# stm32f4-discovery-breakout-v1.net
KiCad netlist of a schematic drawn in EAGLE
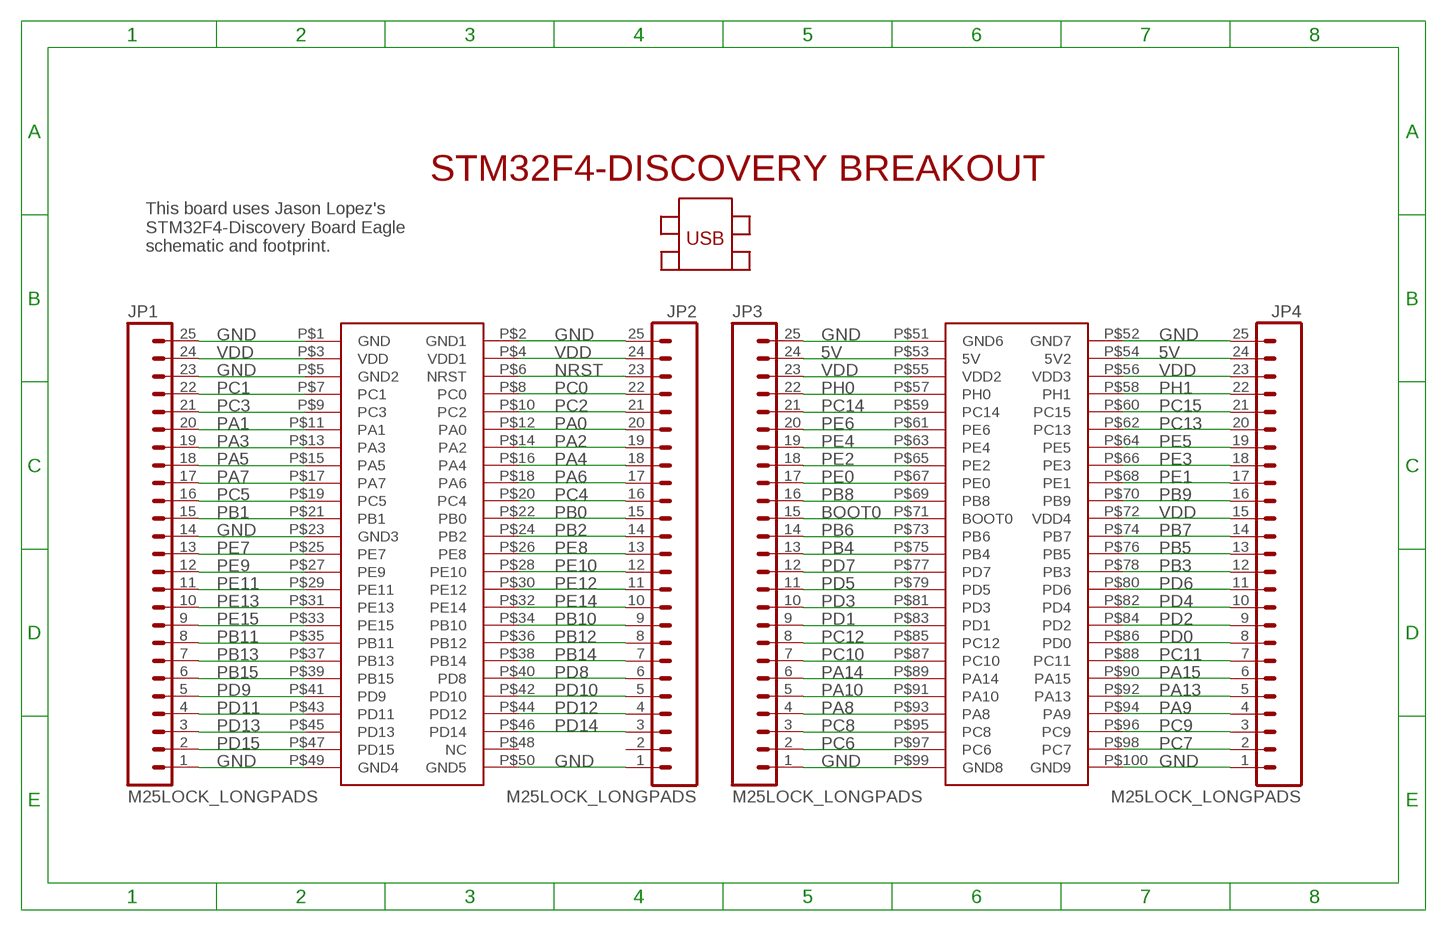
[diagram p0: schematic, sheet 1]

(export (version "E")
  (design (tool "Eeschema 10.0.6"))
  (components
    (comp (ref "JP1")
      (value "M25LOCK_LONGPADS")
      (footprint "eagle-import:1X25_LOCK_LONGPADS")
      (libsource (lib "eagle-import") (part "M25LOCK_LONGPADS"))
    )
    (comp (ref "JP2")
      (value "M25LOCK_LONGPADS")
      (footprint "eagle-import:1X25_LOCK_LONGPADS")
      (libsource (lib "eagle-import") (part "M25LOCK_LONGPADS"))
    )
    (comp (ref "JP3")
      (value "M25LOCK_LONGPADS")
      (footprint "eagle-import:1X25_LOCK_LONGPADS")
      (libsource (lib "eagle-import") (part "M25LOCK_LONGPADS"))
    )
    (comp (ref "JP4")
      (value "M25LOCK_LONGPADS")
      (footprint "eagle-import:1X25_LOCK_LONGPADS")
      (libsource (lib "eagle-import") (part "M25LOCK_LONGPADS"))
    )
    (comp (ref "U$1")
      (value "STM32F4-DISCOVERY")
      (footprint "eagle-import:STM32F4-DISCOVERY")
      (libsource (lib "eagle-import") (part "STM32F4-DISCOVERY"))
    )
  )
  (nets
    (net (code "1") (name "/5V") (class "Default")
      (node (ref "JP3") (pin "24") (pinfunction "24_24") (pintype "passive"))
      (node (ref "JP4") (pin "24") (pinfunction "24_24") (pintype "passive"))
      (node (ref "U$1") (pin "P$53") (pinfunction "5V_P$53") (pintype "bidirectional"))
      (node (ref "U$1") (pin "P$54") (pinfunction "5V2_P$54") (pintype "bidirectional"))
    )
    (net (code "2") (name "/BOOT0") (class "Default")
      (node (ref "JP3") (pin "15") (pinfunction "15_15") (pintype "passive"))
      (node (ref "U$1") (pin "P$71") (pinfunction "BOOT0_P$71") (pintype "bidirectional"))
    )
    (net (code "3") (name "/GND") (class "Default")
      (node (ref "JP1") (pin "1") (pinfunction "1_1") (pintype "passive"))
      (node (ref "JP1") (pin "14") (pinfunction "14_14") (pintype "passive"))
      (node (ref "JP1") (pin "23") (pinfunction "23_23") (pintype "passive"))
      (node (ref "JP1") (pin "25") (pinfunction "25_25") (pintype "passive"))
      (node (ref "JP2") (pin "1") (pinfunction "1_1") (pintype "passive"))
      (node (ref "JP2") (pin "25") (pinfunction "25_25") (pintype "passive"))
      (node (ref "JP3") (pin "1") (pinfunction "1_1") (pintype "passive"))
      (node (ref "JP3") (pin "25") (pinfunction "25_25") (pintype "passive"))
      (node (ref "JP4") (pin "1") (pinfunction "1_1") (pintype "passive"))
      (node (ref "JP4") (pin "25") (pinfunction "25_25") (pintype "passive"))
      (node (ref "U$1") (pin "P$1") (pinfunction "GND_P$1") (pintype "bidirectional"))
      (node (ref "U$1") (pin "P$100") (pinfunction "GND9_P$100") (pintype "bidirectional"))
      (node (ref "U$1") (pin "P$2") (pinfunction "GND1_P$2") (pintype "bidirectional"))
      (node (ref "U$1") (pin "P$23") (pinfunction "GND3_P$23") (pintype "bidirectional"))
      (node (ref "U$1") (pin "P$49") (pinfunction "GND4_P$49") (pintype "bidirectional"))
      (node (ref "U$1") (pin "P$5") (pinfunction "GND2_P$5") (pintype "bidirectional"))
      (node (ref "U$1") (pin "P$50") (pinfunction "GND5_P$50") (pintype "bidirectional"))
      (node (ref "U$1") (pin "P$51") (pinfunction "GND6_P$51") (pintype "bidirectional"))
      (node (ref "U$1") (pin "P$52") (pinfunction "GND7_P$52") (pintype "bidirectional"))
      (node (ref "U$1") (pin "P$99") (pinfunction "GND8_P$99") (pintype "bidirectional"))
    )
    (net (code "4") (name "/NRST") (class "Default")
      (node (ref "JP2") (pin "23") (pinfunction "23_23") (pintype "passive"))
      (node (ref "U$1") (pin "P$6") (pinfunction "NRST_P$6") (pintype "bidirectional"))
    )
    (net (code "5") (name "/PA0") (class "Default")
      (node (ref "JP2") (pin "20") (pinfunction "20_20") (pintype "passive"))
      (node (ref "U$1") (pin "P$12") (pinfunction "PA0_P$12") (pintype "bidirectional"))
    )
    (net (code "6") (name "/PA1") (class "Default")
      (node (ref "JP1") (pin "20") (pinfunction "20_20") (pintype "passive"))
      (node (ref "U$1") (pin "P$11") (pinfunction "PA1_P$11") (pintype "bidirectional"))
    )
    (net (code "7") (name "/PA2") (class "Default")
      (node (ref "JP2") (pin "19") (pinfunction "19_19") (pintype "passive"))
      (node (ref "U$1") (pin "P$14") (pinfunction "PA2_P$14") (pintype "bidirectional"))
    )
    (net (code "8") (name "/PA3") (class "Default")
      (node (ref "JP1") (pin "19") (pinfunction "19_19") (pintype "passive"))
      (node (ref "U$1") (pin "P$13") (pinfunction "PA3_P$13") (pintype "bidirectional"))
    )
    (net (code "9") (name "/PA4") (class "Default")
      (node (ref "JP2") (pin "18") (pinfunction "18_18") (pintype "passive"))
      (node (ref "U$1") (pin "P$16") (pinfunction "PA4_P$16") (pintype "bidirectional"))
    )
    (net (code "10") (name "/PA5") (class "Default")
      (node (ref "JP1") (pin "18") (pinfunction "18_18") (pintype "passive"))
      (node (ref "U$1") (pin "P$15") (pinfunction "PA5_P$15") (pintype "bidirectional"))
    )
    (net (code "11") (name "/PA6") (class "Default")
      (node (ref "JP2") (pin "17") (pinfunction "17_17") (pintype "passive"))
      (node (ref "U$1") (pin "P$18") (pinfunction "PA6_P$18") (pintype "bidirectional"))
    )
    (net (code "12") (name "/PA7") (class "Default")
      (node (ref "JP1") (pin "17") (pinfunction "17_17") (pintype "passive"))
      (node (ref "U$1") (pin "P$17") (pinfunction "PA7_P$17") (pintype "bidirectional"))
    )
    (net (code "13") (name "/PA8") (class "Default")
      (node (ref "JP3") (pin "4") (pinfunction "4_4") (pintype "passive"))
      (node (ref "U$1") (pin "P$93") (pinfunction "PA8_P$93") (pintype "bidirectional"))
    )
    (net (code "14") (name "/PA9") (class "Default")
      (node (ref "JP4") (pin "4") (pinfunction "4_4") (pintype "passive"))
      (node (ref "U$1") (pin "P$94") (pinfunction "PA9_P$94") (pintype "bidirectional"))
    )
    (net (code "15") (name "/PA10") (class "Default")
      (node (ref "JP3") (pin "5") (pinfunction "5_5") (pintype "passive"))
      (node (ref "U$1") (pin "P$91") (pinfunction "PA10_P$91") (pintype "bidirectional"))
    )
    (net (code "16") (name "/PA13") (class "Default")
      (node (ref "JP4") (pin "5") (pinfunction "5_5") (pintype "passive"))
      (node (ref "U$1") (pin "P$92") (pinfunction "PA13_P$92") (pintype "bidirectional"))
    )
    (net (code "17") (name "/PA14") (class "Default")
      (node (ref "JP3") (pin "6") (pinfunction "6_6") (pintype "passive"))
      (node (ref "U$1") (pin "P$89") (pinfunction "PA14_P$89") (pintype "bidirectional"))
    )
    (net (code "18") (name "/PA15") (class "Default")
      (node (ref "JP4") (pin "6") (pinfunction "6_6") (pintype "passive"))
      (node (ref "U$1") (pin "P$90") (pinfunction "PA15_P$90") (pintype "bidirectional"))
    )
    (net (code "19") (name "/PB0") (class "Default")
      (node (ref "JP2") (pin "15") (pinfunction "15_15") (pintype "passive"))
      (node (ref "U$1") (pin "P$22") (pinfunction "PB0_P$22") (pintype "bidirectional"))
    )
    (net (code "20") (name "/PB1") (class "Default")
      (node (ref "JP1") (pin "15") (pinfunction "15_15") (pintype "passive"))
      (node (ref "U$1") (pin "P$21") (pinfunction "PB1_P$21") (pintype "bidirectional"))
    )
    (net (code "21") (name "/PB2") (class "Default")
      (node (ref "JP2") (pin "14") (pinfunction "14_14") (pintype "passive"))
      (node (ref "U$1") (pin "P$24") (pinfunction "PB2_P$24") (pintype "bidirectional"))
    )
    (net (code "22") (name "/PB3") (class "Default")
      (node (ref "JP4") (pin "12") (pinfunction "12_12") (pintype "passive"))
      (node (ref "U$1") (pin "P$78") (pinfunction "PB3_P$78") (pintype "bidirectional"))
    )
    (net (code "23") (name "/PB4") (class "Default")
      (node (ref "JP3") (pin "13") (pinfunction "13_13") (pintype "passive"))
      (node (ref "U$1") (pin "P$75") (pinfunction "PB4_P$75") (pintype "bidirectional"))
    )
    (net (code "24") (name "/PB5") (class "Default")
      (node (ref "JP4") (pin "13") (pinfunction "13_13") (pintype "passive"))
      (node (ref "U$1") (pin "P$76") (pinfunction "PB5_P$76") (pintype "bidirectional"))
    )
    (net (code "25") (name "/PB6") (class "Default")
      (node (ref "JP3") (pin "14") (pinfunction "14_14") (pintype "passive"))
      (node (ref "U$1") (pin "P$73") (pinfunction "PB6_P$73") (pintype "bidirectional"))
    )
    (net (code "26") (name "/PB7") (class "Default")
      (node (ref "JP4") (pin "14") (pinfunction "14_14") (pintype "passive"))
      (node (ref "U$1") (pin "P$74") (pinfunction "PB7_P$74") (pintype "bidirectional"))
    )
    (net (code "27") (name "/PB8") (class "Default")
      (node (ref "JP3") (pin "16") (pinfunction "16_16") (pintype "passive"))
      (node (ref "U$1") (pin "P$69") (pinfunction "PB8_P$69") (pintype "bidirectional"))
    )
    (net (code "28") (name "/PB9") (class "Default")
      (node (ref "JP4") (pin "16") (pinfunction "16_16") (pintype "passive"))
      (node (ref "U$1") (pin "P$70") (pinfunction "PB9_P$70") (pintype "bidirectional"))
    )
    (net (code "29") (name "/PB10") (class "Default")
      (node (ref "JP2") (pin "9") (pinfunction "9_9") (pintype "passive"))
      (node (ref "U$1") (pin "P$34") (pinfunction "PB10_P$34") (pintype "bidirectional"))
    )
    (net (code "30") (name "/PB11") (class "Default")
      (node (ref "JP1") (pin "8") (pinfunction "8_8") (pintype "passive"))
      (node (ref "U$1") (pin "P$35") (pinfunction "PB11_P$35") (pintype "bidirectional"))
    )
    (net (code "31") (name "/PB12") (class "Default")
      (node (ref "JP2") (pin "8") (pinfunction "8_8") (pintype "passive"))
      (node (ref "U$1") (pin "P$36") (pinfunction "PB12_P$36") (pintype "bidirectional"))
    )
    (net (code "32") (name "/PB13") (class "Default")
      (node (ref "JP1") (pin "7") (pinfunction "7_7") (pintype "passive"))
      (node (ref "U$1") (pin "P$37") (pinfunction "PB13_P$37") (pintype "bidirectional"))
    )
    (net (code "33") (name "/PB14") (class "Default")
      (node (ref "JP2") (pin "7") (pinfunction "7_7") (pintype "passive"))
      (node (ref "U$1") (pin "P$38") (pinfunction "PB14_P$38") (pintype "bidirectional"))
    )
    (net (code "34") (name "/PB15") (class "Default")
      (node (ref "JP1") (pin "6") (pinfunction "6_6") (pintype "passive"))
      (node (ref "U$1") (pin "P$39") (pinfunction "PB15_P$39") (pintype "bidirectional"))
    )
    (net (code "35") (name "/PC0") (class "Default")
      (node (ref "JP2") (pin "22") (pinfunction "22_22") (pintype "passive"))
      (node (ref "U$1") (pin "P$8") (pinfunction "PC0_P$8") (pintype "bidirectional"))
    )
    (net (code "36") (name "/PC1") (class "Default")
      (node (ref "JP1") (pin "22") (pinfunction "22_22") (pintype "passive"))
      (node (ref "U$1") (pin "P$7") (pinfunction "PC1_P$7") (pintype "bidirectional"))
    )
    (net (code "37") (name "/PC2") (class "Default")
      (node (ref "JP2") (pin "21") (pinfunction "21_21") (pintype "passive"))
      (node (ref "U$1") (pin "P$10") (pinfunction "PC2_P$10") (pintype "bidirectional"))
    )
    (net (code "38") (name "/PC3") (class "Default")
      (node (ref "JP1") (pin "21") (pinfunction "21_21") (pintype "passive"))
      (node (ref "U$1") (pin "P$9") (pinfunction "PC3_P$9") (pintype "bidirectional"))
    )
    (net (code "39") (name "/PC4") (class "Default")
      (node (ref "JP2") (pin "16") (pinfunction "16_16") (pintype "passive"))
      (node (ref "U$1") (pin "P$20") (pinfunction "PC4_P$20") (pintype "bidirectional"))
    )
    (net (code "40") (name "/PC5") (class "Default")
      (node (ref "JP1") (pin "16") (pinfunction "16_16") (pintype "passive"))
      (node (ref "U$1") (pin "P$19") (pinfunction "PC5_P$19") (pintype "bidirectional"))
    )
    (net (code "41") (name "/PC6") (class "Default")
      (node (ref "JP3") (pin "2") (pinfunction "2_2") (pintype "passive"))
      (node (ref "U$1") (pin "P$97") (pinfunction "PC6_P$97") (pintype "bidirectional"))
    )
    (net (code "42") (name "/PC7") (class "Default")
      (node (ref "JP4") (pin "2") (pinfunction "2_2") (pintype "passive"))
      (node (ref "U$1") (pin "P$98") (pinfunction "PC7_P$98") (pintype "bidirectional"))
    )
    (net (code "43") (name "/PC8") (class "Default")
      (node (ref "JP3") (pin "3") (pinfunction "3_3") (pintype "passive"))
      (node (ref "U$1") (pin "P$95") (pinfunction "PC8_P$95") (pintype "bidirectional"))
    )
    (net (code "44") (name "/PC9") (class "Default")
      (node (ref "JP4") (pin "3") (pinfunction "3_3") (pintype "passive"))
      (node (ref "U$1") (pin "P$96") (pinfunction "PC9_P$96") (pintype "bidirectional"))
    )
    (net (code "45") (name "/PC10") (class "Default")
      (node (ref "JP3") (pin "7") (pinfunction "7_7") (pintype "passive"))
      (node (ref "U$1") (pin "P$87") (pinfunction "PC10_P$87") (pintype "bidirectional"))
    )
    (net (code "46") (name "/PC11") (class "Default")
      (node (ref "JP4") (pin "7") (pinfunction "7_7") (pintype "passive"))
      (node (ref "U$1") (pin "P$88") (pinfunction "PC11_P$88") (pintype "bidirectional"))
    )
    (net (code "47") (name "/PC12") (class "Default")
      (node (ref "JP3") (pin "8") (pinfunction "8_8") (pintype "passive"))
      (node (ref "U$1") (pin "P$85") (pinfunction "PC12_P$85") (pintype "bidirectional"))
    )
    (net (code "48") (name "/PC13") (class "Default")
      (node (ref "JP4") (pin "20") (pinfunction "20_20") (pintype "passive"))
      (node (ref "U$1") (pin "P$62") (pinfunction "PC13_P$62") (pintype "bidirectional"))
    )
    (net (code "49") (name "/PC14") (class "Default")
      (node (ref "JP3") (pin "21") (pinfunction "21_21") (pintype "passive"))
      (node (ref "U$1") (pin "P$59") (pinfunction "PC14_P$59") (pintype "bidirectional"))
    )
    (net (code "50") (name "/PC15") (class "Default")
      (node (ref "JP4") (pin "21") (pinfunction "21_21") (pintype "passive"))
      (node (ref "U$1") (pin "P$60") (pinfunction "PC15_P$60") (pintype "bidirectional"))
    )
    (net (code "51") (name "/PD0") (class "Default")
      (node (ref "JP4") (pin "8") (pinfunction "8_8") (pintype "passive"))
      (node (ref "U$1") (pin "P$86") (pinfunction "PD0_P$86") (pintype "bidirectional"))
    )
    (net (code "52") (name "/PD1") (class "Default")
      (node (ref "JP3") (pin "9") (pinfunction "9_9") (pintype "passive"))
      (node (ref "U$1") (pin "P$83") (pinfunction "PD1_P$83") (pintype "bidirectional"))
    )
    (net (code "53") (name "/PD2") (class "Default")
      (node (ref "JP4") (pin "9") (pinfunction "9_9") (pintype "passive"))
      (node (ref "U$1") (pin "P$84") (pinfunction "PD2_P$84") (pintype "bidirectional"))
    )
    (net (code "54") (name "/PD3") (class "Default")
      (node (ref "JP3") (pin "10") (pinfunction "10_10") (pintype "passive"))
      (node (ref "U$1") (pin "P$81") (pinfunction "PD3_P$81") (pintype "bidirectional"))
    )
    (net (code "55") (name "/PD4") (class "Default")
      (node (ref "JP4") (pin "10") (pinfunction "10_10") (pintype "passive"))
      (node (ref "U$1") (pin "P$82") (pinfunction "PD4_P$82") (pintype "bidirectional"))
    )
    (net (code "56") (name "/PD5") (class "Default")
      (node (ref "JP3") (pin "11") (pinfunction "11_11") (pintype "passive"))
      (node (ref "U$1") (pin "P$79") (pinfunction "PD5_P$79") (pintype "bidirectional"))
    )
    (net (code "57") (name "/PD6") (class "Default")
      (node (ref "JP4") (pin "11") (pinfunction "11_11") (pintype "passive"))
      (node (ref "U$1") (pin "P$80") (pinfunction "PD6_P$80") (pintype "bidirectional"))
    )
    (net (code "58") (name "/PD7") (class "Default")
      (node (ref "JP3") (pin "12") (pinfunction "12_12") (pintype "passive"))
      (node (ref "U$1") (pin "P$77") (pinfunction "PD7_P$77") (pintype "bidirectional"))
    )
    (net (code "59") (name "/PD8") (class "Default")
      (node (ref "JP2") (pin "6") (pinfunction "6_6") (pintype "passive"))
      (node (ref "U$1") (pin "P$40") (pinfunction "PD8_P$40") (pintype "bidirectional"))
    )
    (net (code "60") (name "/PD9") (class "Default")
      (node (ref "JP1") (pin "5") (pinfunction "5_5") (pintype "passive"))
      (node (ref "U$1") (pin "P$41") (pinfunction "PD9_P$41") (pintype "bidirectional"))
    )
    (net (code "61") (name "/PD10") (class "Default")
      (node (ref "JP2") (pin "5") (pinfunction "5_5") (pintype "passive"))
      (node (ref "U$1") (pin "P$42") (pinfunction "PD10_P$42") (pintype "bidirectional"))
    )
    (net (code "62") (name "/PD11") (class "Default")
      (node (ref "JP1") (pin "4") (pinfunction "4_4") (pintype "passive"))
      (node (ref "U$1") (pin "P$43") (pinfunction "PD11_P$43") (pintype "bidirectional"))
    )
    (net (code "63") (name "/PD12") (class "Default")
      (node (ref "JP2") (pin "4") (pinfunction "4_4") (pintype "passive"))
      (node (ref "U$1") (pin "P$44") (pinfunction "PD12_P$44") (pintype "bidirectional"))
    )
    (net (code "64") (name "/PD13") (class "Default")
      (node (ref "JP1") (pin "3") (pinfunction "3_3") (pintype "passive"))
      (node (ref "U$1") (pin "P$45") (pinfunction "PD13_P$45") (pintype "bidirectional"))
    )
    (net (code "65") (name "/PD14") (class "Default")
      (node (ref "JP2") (pin "3") (pinfunction "3_3") (pintype "passive"))
      (node (ref "U$1") (pin "P$46") (pinfunction "PD14_P$46") (pintype "bidirectional"))
    )
    (net (code "66") (name "/PD15") (class "Default")
      (node (ref "JP1") (pin "2") (pinfunction "2_2") (pintype "passive"))
      (node (ref "U$1") (pin "P$47") (pinfunction "PD15_P$47") (pintype "bidirectional"))
    )
    (net (code "67") (name "/PE0") (class "Default")
      (node (ref "JP3") (pin "17") (pinfunction "17_17") (pintype "passive"))
      (node (ref "U$1") (pin "P$67") (pinfunction "PE0_P$67") (pintype "bidirectional"))
    )
    (net (code "68") (name "/PE1") (class "Default")
      (node (ref "JP4") (pin "17") (pinfunction "17_17") (pintype "passive"))
      (node (ref "U$1") (pin "P$68") (pinfunction "PE1_P$68") (pintype "bidirectional"))
    )
    (net (code "69") (name "/PE2") (class "Default")
      (node (ref "JP3") (pin "18") (pinfunction "18_18") (pintype "passive"))
      (node (ref "U$1") (pin "P$65") (pinfunction "PE2_P$65") (pintype "bidirectional"))
    )
    (net (code "70") (name "/PE3") (class "Default")
      (node (ref "JP4") (pin "18") (pinfunction "18_18") (pintype "passive"))
      (node (ref "U$1") (pin "P$66") (pinfunction "PE3_P$66") (pintype "bidirectional"))
    )
    (net (code "71") (name "/PE4") (class "Default")
      (node (ref "JP3") (pin "19") (pinfunction "19_19") (pintype "passive"))
      (node (ref "U$1") (pin "P$63") (pinfunction "PE4_P$63") (pintype "bidirectional"))
    )
    (net (code "72") (name "/PE5") (class "Default")
      (node (ref "JP4") (pin "19") (pinfunction "19_19") (pintype "passive"))
      (node (ref "U$1") (pin "P$64") (pinfunction "PE5_P$64") (pintype "bidirectional"))
    )
    (net (code "73") (name "/PE6") (class "Default")
      (node (ref "JP3") (pin "20") (pinfunction "20_20") (pintype "passive"))
      (node (ref "U$1") (pin "P$61") (pinfunction "PE6_P$61") (pintype "bidirectional"))
    )
    (net (code "74") (name "/PE7") (class "Default")
      (node (ref "JP1") (pin "13") (pinfunction "13_13") (pintype "passive"))
      (node (ref "U$1") (pin "P$25") (pinfunction "PE7_P$25") (pintype "bidirectional"))
    )
    (net (code "75") (name "/PE8") (class "Default")
      (node (ref "JP2") (pin "13") (pinfunction "13_13") (pintype "passive"))
      (node (ref "U$1") (pin "P$26") (pinfunction "PE8_P$26") (pintype "bidirectional"))
    )
    (net (code "76") (name "/PE9") (class "Default")
      (node (ref "JP1") (pin "12") (pinfunction "12_12") (pintype "passive"))
      (node (ref "U$1") (pin "P$27") (pinfunction "PE9_P$27") (pintype "bidirectional"))
    )
    (net (code "77") (name "/PE10") (class "Default")
      (node (ref "JP2") (pin "12") (pinfunction "12_12") (pintype "passive"))
      (node (ref "U$1") (pin "P$28") (pinfunction "PE10_P$28") (pintype "bidirectional"))
    )
    (net (code "78") (name "/PE11") (class "Default")
      (node (ref "JP1") (pin "11") (pinfunction "11_11") (pintype "passive"))
      (node (ref "U$1") (pin "P$29") (pinfunction "PE11_P$29") (pintype "bidirectional"))
    )
    (net (code "79") (name "/PE12") (class "Default")
      (node (ref "JP2") (pin "11") (pinfunction "11_11") (pintype "passive"))
      (node (ref "U$1") (pin "P$30") (pinfunction "PE12_P$30") (pintype "bidirectional"))
    )
    (net (code "80") (name "/PE13") (class "Default")
      (node (ref "JP1") (pin "10") (pinfunction "10_10") (pintype "passive"))
      (node (ref "U$1") (pin "P$31") (pinfunction "PE13_P$31") (pintype "bidirectional"))
    )
    (net (code "81") (name "/PE14") (class "Default")
      (node (ref "JP2") (pin "10") (pinfunction "10_10") (pintype "passive"))
      (node (ref "U$1") (pin "P$32") (pinfunction "PE14_P$32") (pintype "bidirectional"))
    )
    (net (code "82") (name "/PE15") (class "Default")
      (node (ref "JP1") (pin "9") (pinfunction "9_9") (pintype "passive"))
      (node (ref "U$1") (pin "P$33") (pinfunction "PE15_P$33") (pintype "bidirectional"))
    )
    (net (code "83") (name "/PH0") (class "Default")
      (node (ref "JP3") (pin "22") (pinfunction "22_22") (pintype "passive"))
      (node (ref "U$1") (pin "P$57") (pinfunction "PH0_P$57") (pintype "bidirectional"))
    )
    (net (code "84") (name "/PH1") (class "Default")
      (node (ref "JP4") (pin "22") (pinfunction "22_22") (pintype "passive"))
      (node (ref "U$1") (pin "P$58") (pinfunction "PH1_P$58") (pintype "bidirectional"))
    )
    (net (code "85") (name "/VDD") (class "Default")
      (node (ref "JP1") (pin "24") (pinfunction "24_24") (pintype "passive"))
      (node (ref "JP2") (pin "24") (pinfunction "24_24") (pintype "passive"))
      (node (ref "JP3") (pin "23") (pinfunction "23_23") (pintype "passive"))
      (node (ref "JP4") (pin "15") (pinfunction "15_15") (pintype "passive"))
      (node (ref "JP4") (pin "23") (pinfunction "23_23") (pintype "passive"))
      (node (ref "U$1") (pin "P$3") (pinfunction "VDD_P$3") (pintype "bidirectional"))
      (node (ref "U$1") (pin "P$4") (pinfunction "VDD1_P$4") (pintype "bidirectional"))
      (node (ref "U$1") (pin "P$55") (pinfunction "VDD2_P$55") (pintype "bidirectional"))
      (node (ref "U$1") (pin "P$56") (pinfunction "VDD3_P$56") (pintype "bidirectional"))
      (node (ref "U$1") (pin "P$72") (pinfunction "VDD4_P$72") (pintype "bidirectional"))
    )
    (net (code "86") (name "unconnected-(JP2-Pad2)") (class "Default")
      (node (ref "JP2") (pin "2") (pinfunction "2_2") (pintype "passive"))
    )
    (net (code "87") (name "unconnected-(U$1-NC-PadP$48)") (class "Default")
      (node (ref "U$1") (pin "P$48") (pinfunction "NC_P$48") (pintype "bidirectional"))
    )
  )
)
